# sensing_unit_rev2.net
KiCad netlist of a schematic drawn in EAGLE
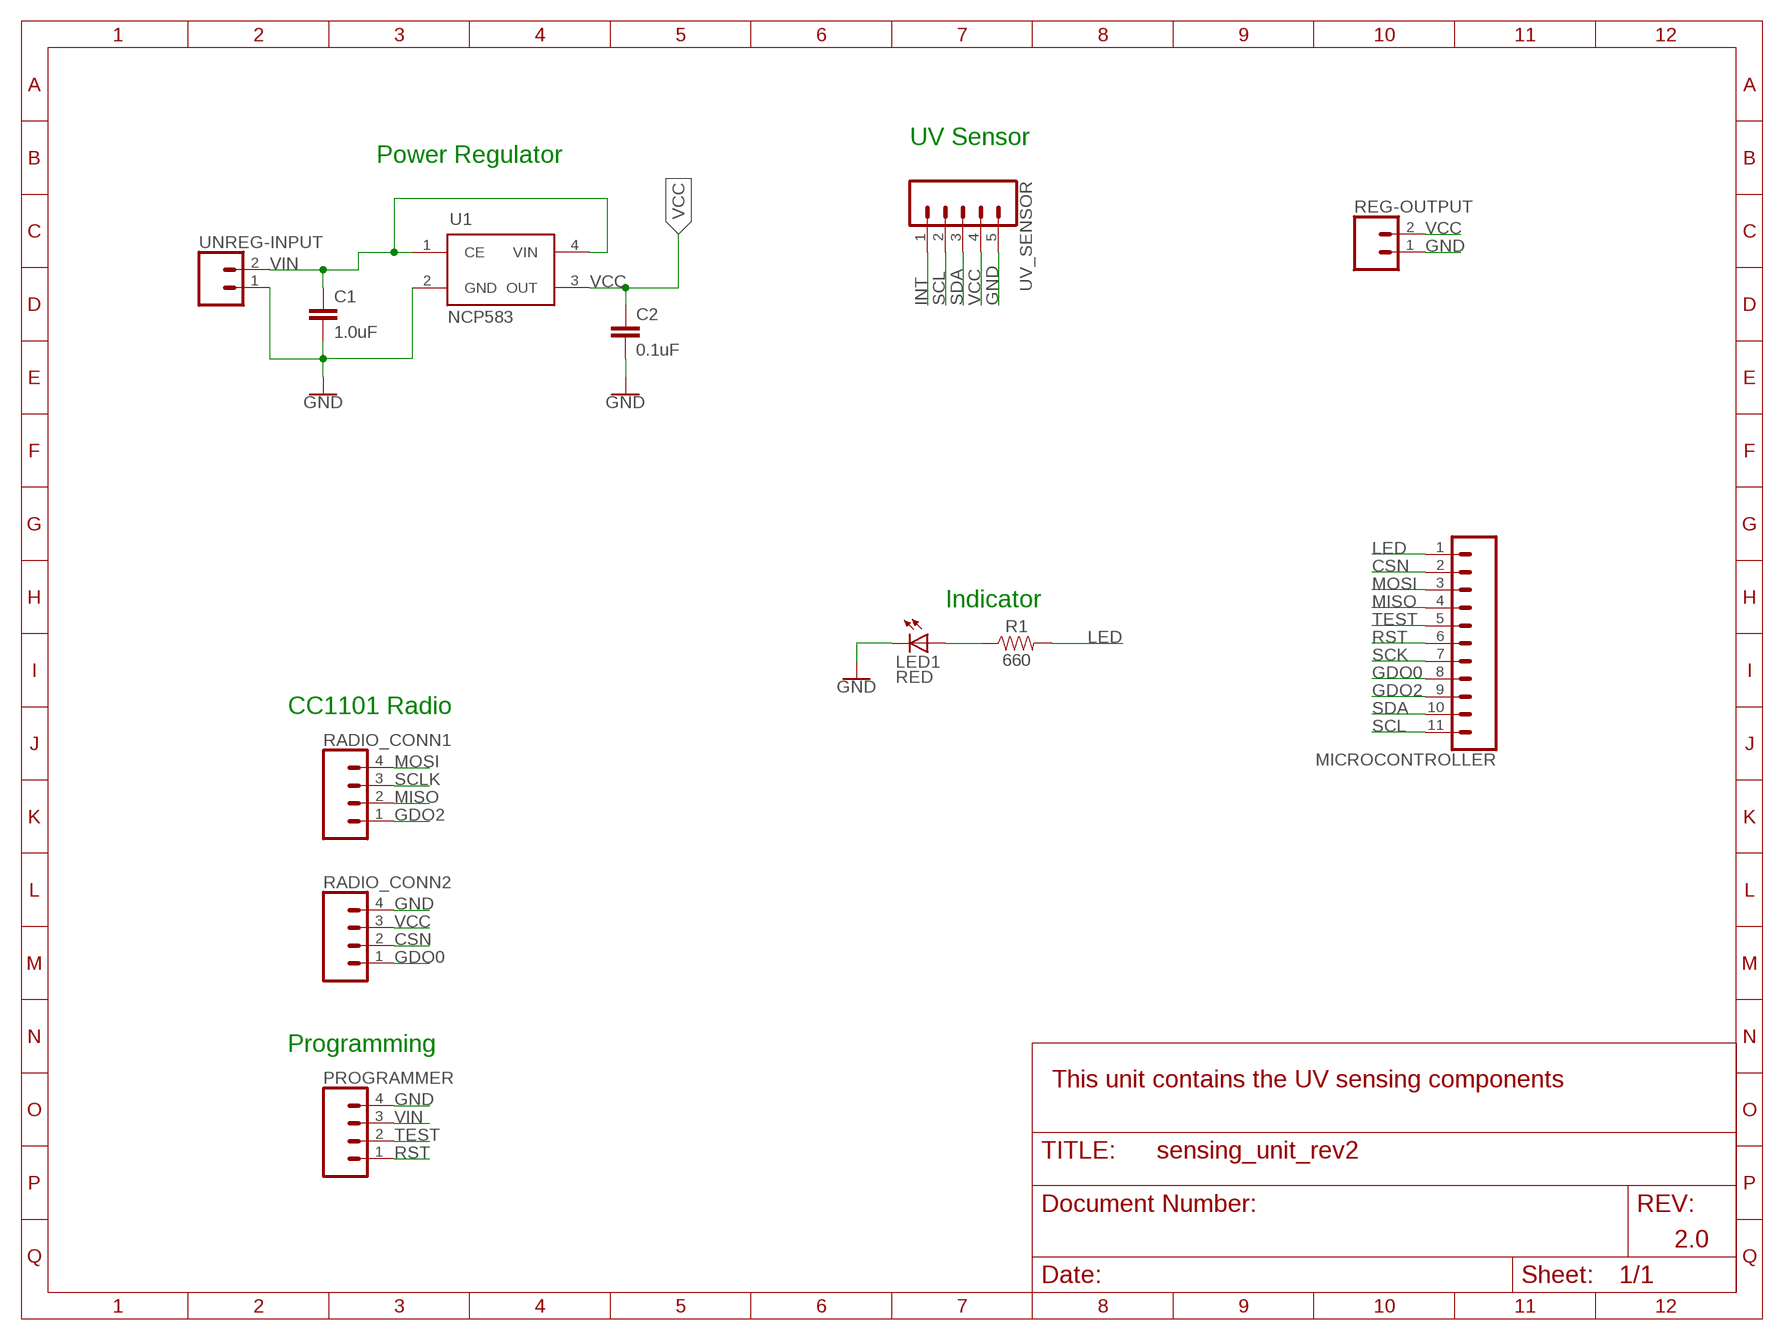
[diagram p0: schematic, sheet 1]

(export (version "E")
  (design (tool "Eeschema 10.0.6"))
  (components
    (comp (ref "C1")
      (value "1.0uF")
      (footprint "eagle-import:0805")
      (libsource (lib "eagle-import") (part "1.0UF-0805-25V-(+80/-20%)"))
    )
    (comp (ref "C2")
      (value "0.1uF")
      (footprint "eagle-import:0805")
      (libsource (lib "eagle-import") (part "1.0UF-0805-25V-(+80/-20%)"))
    )
    (comp (ref "LED1")
      (value "RED")
      (footprint "eagle-import:CHIP-LED0805")
      (libsource (lib "eagle-import") (part "LEDCHIP-LED0805"))
    )
    (comp (ref "MICROCONTROLLER")
      (value "CONN_11")
      (footprint "eagle-import:1X11")
      (libsource (lib "eagle-import") (part "CONN_11"))
    )
    (comp (ref "PROGRAMMER")
      (value "CONN_04")
      (footprint "eagle-import:1X04")
      (libsource (lib "eagle-import") (part "CONN_04"))
    )
    (comp (ref "R1")
      (value "660")
      (footprint "eagle-import:0805")
      (libsource (lib "eagle-import") (part "RESISTOR0805"))
    )
    (comp (ref "RADIO_CONN1")
      (value "CONN_04")
      (footprint "eagle-import:1X04")
      (libsource (lib "eagle-import") (part "CONN_04"))
    )
    (comp (ref "RADIO_CONN2")
      (value "CONN_04")
      (footprint "eagle-import:1X04")
      (libsource (lib "eagle-import") (part "CONN_04"))
    )
    (comp (ref "REG-OUTPUT")
      (value "CONN_02")
      (footprint "eagle-import:1X02")
      (libsource (lib "eagle-import") (part "CONN_02"))
    )
    (comp (ref "U1")
      (value "NCP583")
      (footprint "eagle-import:SC82-AB_1PRIMARY")
      (libsource (lib "eagle-import") (part "NCP583"))
    )
    (comp (ref "UNREG-INPUT")
      (value "CONN_02")
      (footprint "eagle-import:1X02")
      (libsource (lib "eagle-import") (part "CONN_02"))
    )
    (comp (ref "UV_SENSOR")
      (value "CONN_05")
      (footprint "eagle-import:1X05")
      (libsource (lib "eagle-import") (part "CONN_05"))
    )
  )
  (nets
    (net (code "1") (name "/CSN") (class "Default")
      (node (ref "MICROCONTROLLER") (pin "2") (pinfunction "2_2") (pintype "passive"))
      (node (ref "RADIO_CONN2") (pin "2") (pinfunction "2_2") (pintype "passive"))
    )
    (net (code "2") (name "/GDO0") (class "Default")
      (node (ref "MICROCONTROLLER") (pin "8") (pinfunction "8_8") (pintype "passive"))
      (node (ref "RADIO_CONN2") (pin "1") (pinfunction "1_1") (pintype "passive"))
    )
    (net (code "3") (name "/GDO2") (class "Default")
      (node (ref "MICROCONTROLLER") (pin "9") (pinfunction "9_9") (pintype "passive"))
      (node (ref "RADIO_CONN1") (pin "1") (pinfunction "1_1") (pintype "passive"))
    )
    (net (code "4") (name "/INT") (class "Default")
      (node (ref "UV_SENSOR") (pin "1") (pinfunction "1_1") (pintype "passive"))
    )
    (net (code "5") (name "/LED") (class "Default")
      (node (ref "MICROCONTROLLER") (pin "1") (pinfunction "1_1") (pintype "passive"))
      (node (ref "R1") (pin "2") (pinfunction "2_2") (pintype "passive"))
    )
    (net (code "6") (name "/MISO") (class "Default")
      (node (ref "MICROCONTROLLER") (pin "4") (pinfunction "4_4") (pintype "passive"))
      (node (ref "RADIO_CONN1") (pin "2") (pinfunction "2_2") (pintype "passive"))
    )
    (net (code "7") (name "/MOSI") (class "Default")
      (node (ref "MICROCONTROLLER") (pin "3") (pinfunction "3_3") (pintype "passive"))
      (node (ref "RADIO_CONN1") (pin "4") (pinfunction "4_4") (pintype "passive"))
    )
    (net (code "8") (name "/RST") (class "Default")
      (node (ref "MICROCONTROLLER") (pin "6") (pinfunction "6_6") (pintype "passive"))
      (node (ref "PROGRAMMER") (pin "1") (pinfunction "1_1") (pintype "passive"))
    )
    (net (code "9") (name "/SCK") (class "Default")
      (node (ref "MICROCONTROLLER") (pin "7") (pinfunction "7_7") (pintype "passive"))
    )
    (net (code "10") (name "/SCL") (class "Default")
      (node (ref "MICROCONTROLLER") (pin "11") (pinfunction "11_11") (pintype "passive"))
      (node (ref "UV_SENSOR") (pin "2") (pinfunction "2_2") (pintype "passive"))
    )
    (net (code "11") (name "/SCLK") (class "Default")
      (node (ref "RADIO_CONN1") (pin "3") (pinfunction "3_3") (pintype "passive"))
    )
    (net (code "12") (name "/SDA") (class "Default")
      (node (ref "MICROCONTROLLER") (pin "10") (pinfunction "10_10") (pintype "passive"))
      (node (ref "UV_SENSOR") (pin "3") (pinfunction "3_3") (pintype "passive"))
    )
    (net (code "13") (name "/TEST") (class "Default")
      (node (ref "MICROCONTROLLER") (pin "5") (pinfunction "5_5") (pintype "passive"))
      (node (ref "PROGRAMMER") (pin "2") (pinfunction "2_2") (pintype "passive"))
    )
    (net (code "14") (name "/VIN") (class "Default")
      (node (ref "C1") (pin "1") (pinfunction "1_1") (pintype "passive"))
      (node (ref "PROGRAMMER") (pin "3") (pinfunction "3_3") (pintype "passive"))
      (node (ref "U1") (pin "1") (pinfunction "CE_1") (pintype "bidirectional"))
      (node (ref "U1") (pin "4") (pinfunction "VIN_4") (pintype "bidirectional"))
      (node (ref "UNREG-INPUT") (pin "2") (pinfunction "2_2") (pintype "passive"))
    )
    (net (code "15") (name "GND") (class "Default")
      (node (ref "C1") (pin "2") (pinfunction "2_2") (pintype "passive"))
      (node (ref "C2") (pin "2") (pinfunction "2_2") (pintype "passive"))
      (node (ref "LED1") (pin "C") (pinfunction "C_C") (pintype "passive"))
      (node (ref "PROGRAMMER") (pin "4") (pinfunction "4_4") (pintype "passive"))
      (node (ref "RADIO_CONN2") (pin "4") (pinfunction "4_4") (pintype "passive"))
      (node (ref "REG-OUTPUT") (pin "1") (pinfunction "1_1") (pintype "passive"))
      (node (ref "U1") (pin "2") (pinfunction "GND_2") (pintype "bidirectional"))
      (node (ref "UNREG-INPUT") (pin "1") (pinfunction "1_1") (pintype "passive"))
      (node (ref "UV_SENSOR") (pin "5") (pinfunction "5_5") (pintype "passive"))
    )
    (net (code "16") (name "Net-(LED1-PadA)") (class "Default")
      (node (ref "LED1") (pin "A") (pinfunction "A_A") (pintype "passive"))
      (node (ref "R1") (pin "1") (pinfunction "1_1") (pintype "passive"))
    )
    (net (code "17") (name "VCC") (class "Default")
      (node (ref "C2") (pin "1") (pinfunction "1_1") (pintype "passive"))
      (node (ref "RADIO_CONN2") (pin "3") (pinfunction "3_3") (pintype "passive"))
      (node (ref "REG-OUTPUT") (pin "2") (pinfunction "2_2") (pintype "passive"))
      (node (ref "U1") (pin "3") (pinfunction "OUT_3") (pintype "bidirectional"))
      (node (ref "UV_SENSOR") (pin "4") (pinfunction "4_4") (pintype "passive"))
    )
  )
)
